# LB-word-oscillator.net
KiCad netlist of a schematic drawn in Altium Designer
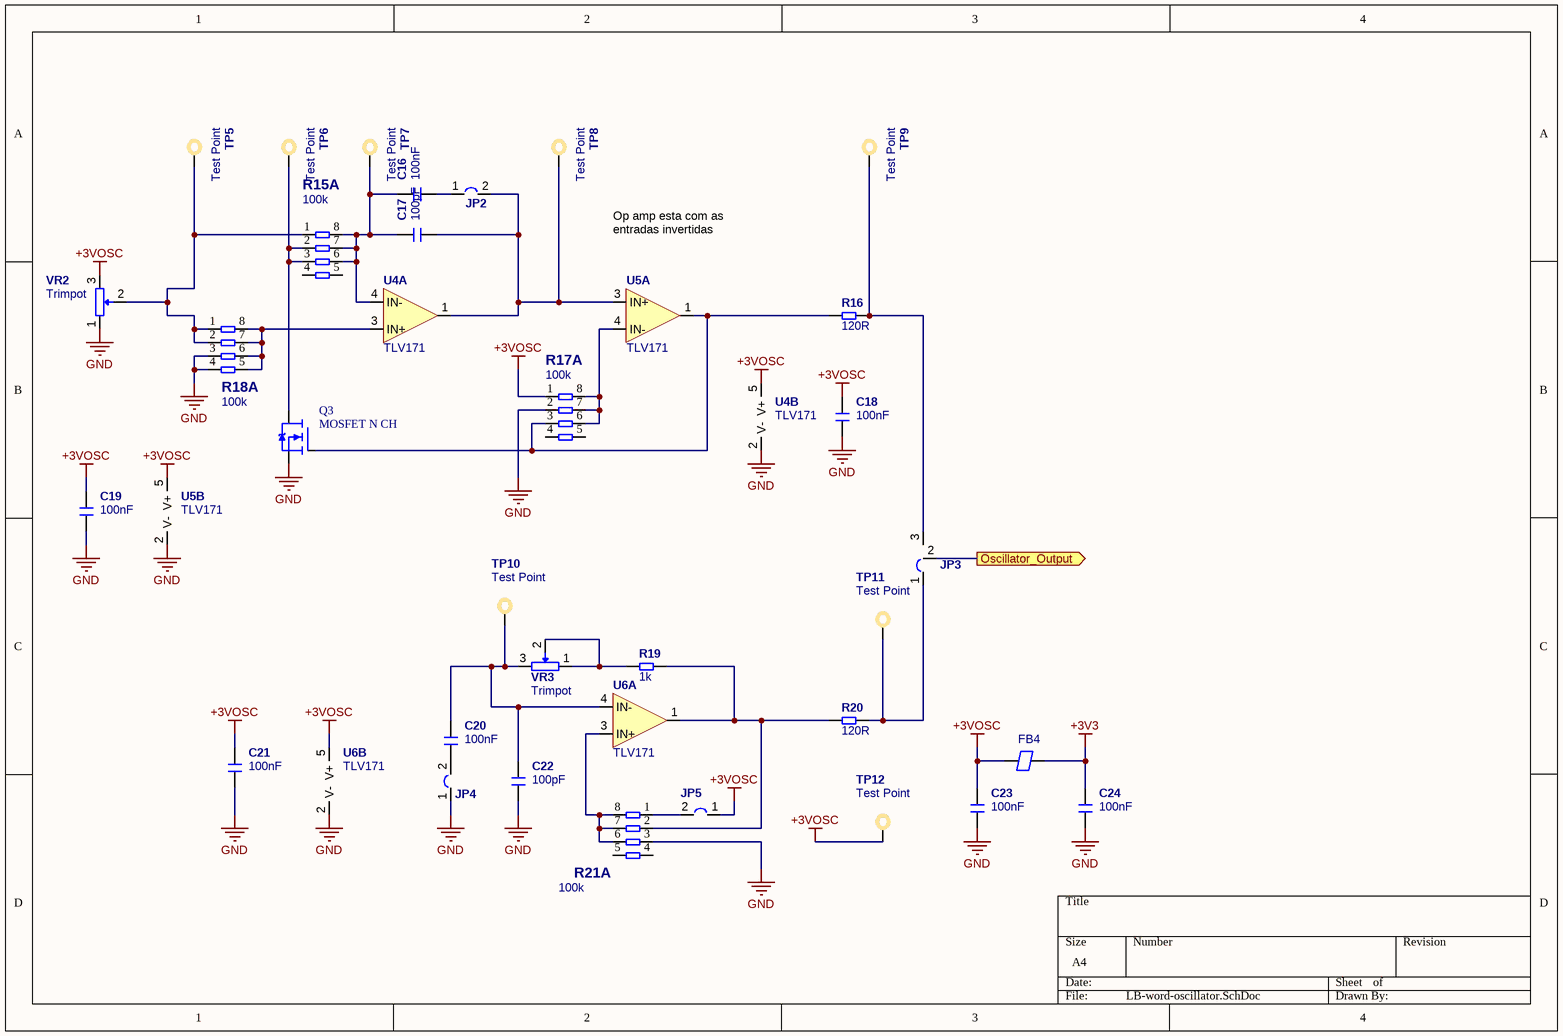
[diagram p0: LB-word-oscillator.SchDoc]

(export (version "E")
  (design (tool "Eeschema 10.0.6"))
  (components
    (comp (ref "C16")
      (value "100nF")
      (footprint "C0603_N")
      (description "Capacitor MLCC")
      (fields
        (field (name "MANUFACTURER") "Yageo")
        (field (name "MANUFACTURER PART NUMBER") "CC0603KRX7R9BB104")
      )
      (libsource (lib "wes") (part "Capacitor"))
    )
    (comp (ref "C17")
      (value "100pF")
      (footprint "C0603_N")
      (description "Capacitor MLCC")
      (fields
        (field (name "MANUFACTURER") "Yageo")
        (field (name "MANUFACTURER PART NUMBER") "CC0603KRX7R9BB104")
      )
      (libsource (lib "wes") (part "Capacitor"))
    )
    (comp (ref "C18")
      (value "100nF")
      (footprint "C0603_N")
      (description "Capacitor MLCC")
      (fields
        (field (name "MANUFACTURER") "Yageo")
        (field (name "MANUFACTURER PART NUMBER") "CC0603KRX7R9BB104")
      )
      (libsource (lib "wes") (part "Capacitor"))
    )
    (comp (ref "C19")
      (value "100nF")
      (footprint "C0603_N")
      (description "Capacitor MLCC")
      (fields
        (field (name "MANUFACTURER") "Yageo")
        (field (name "MANUFACTURER PART NUMBER") "CC0603KRX7R9BB104")
      )
      (libsource (lib "wes") (part "Capacitor"))
    )
    (comp (ref "C20")
      (value "100nF")
      (footprint "C0603_N")
      (description "Capacitor MLCC")
      (fields
        (field (name "MANUFACTURER") "Yageo")
        (field (name "MANUFACTURER PART NUMBER") "CC0603KRX7R9BB104")
      )
      (libsource (lib "wes") (part "Capacitor"))
    )
    (comp (ref "C21")
      (value "100nF")
      (footprint "C0603_N")
      (description "Capacitor MLCC")
      (fields
        (field (name "MANUFACTURER") "Yageo")
        (field (name "MANUFACTURER PART NUMBER") "CC0603KRX7R9BB104")
      )
      (libsource (lib "wes") (part "Capacitor"))
    )
    (comp (ref "C22")
      (value "100pF")
      (footprint "C0603_N")
      (description "Capacitor MLCC")
      (fields
        (field (name "MANUFACTURER") "Yageo")
        (field (name "MANUFACTURER PART NUMBER") "CC0603KRX7R9BB104")
      )
      (libsource (lib "wes") (part "Capacitor"))
    )
    (comp (ref "C23")
      (value "100nF")
      (footprint "C0603_N")
      (description "Capacitor MLCC")
      (fields
        (field (name "MANUFACTURER") "Yageo")
        (field (name "MANUFACTURER PART NUMBER") "CC0603KRX7R9BB104")
      )
      (libsource (lib "wes") (part "Capacitor"))
    )
    (comp (ref "C24")
      (value "100nF")
      (footprint "C0603_N")
      (description "Capacitor MLCC")
      (fields
        (field (name "MANUFACTURER") "Yageo")
        (field (name "MANUFACTURER PART NUMBER") "CC0603KRX7R9BB104")
      )
      (libsource (lib "wes") (part "Capacitor"))
    )
    (comp (ref "FB4")
      (value "Ferrite Bead")
      (footprint "F0603_N")
      (libsource (lib "wes") (part "Ferrite Bead"))
    )
    (comp (ref "JP2")
      (value "Jumper 2W")
      (footprint "Jumper SMD 2W NO")
      (libsource (lib "") (part "Jumper 2W_1"))
    )
    (comp (ref "JP3")
      (value "Jumper 3W")
      (footprint "Jumper SMD 3W NO")
      (libsource (lib "wes") (part "Jumper 3W"))
    )
    (comp (ref "JP4")
      (value "Jumper 2W")
      (footprint "Jumper SMD 2W NO")
      (libsource (lib "") (part "Jumper 2W_1"))
    )
    (comp (ref "JP5")
      (value "Jumper 2W")
      (footprint "Jumper SMD 2W NO")
      (libsource (lib "wes") (part "Jumper 2W"))
    )
    (comp (ref "Q3") (value "MOSFET N CH") (footprint "SOT23_N") (libsource (lib "wes") (part "MOSFET N CH")))
    (comp (ref "R15")
      (value "100k")
      (footprint "YC164")
      (fields (field (name "Comment") "; 100k"))
      (libsource (lib "wes") (part "Resistor Array - 4P"))
    )
    (comp (ref "R16")
      (value "120R")
      (footprint "R0603")
      (fields (field (name "PUBLISHER") "Altium Limited"))
      (libsource (lib "wes") (part "Resistor"))
    )
    (comp (ref "R17")
      (value "100k")
      (footprint "YC164")
      (fields (field (name "Comment") "; 100k"))
      (libsource (lib "wes") (part "Resistor Array - 4P"))
    )
    (comp (ref "R18")
      (value "100k")
      (footprint "YC164")
      (fields (field (name "Comment") "; 100k"))
      (libsource (lib "wes") (part "Resistor Array - 4P"))
    )
    (comp (ref "R19")
      (value "1k")
      (footprint "R0603")
      (fields (field (name "PUBLISHER") "Altium Limited"))
      (libsource (lib "wes") (part "Resistor"))
    )
    (comp (ref "R20")
      (value "120R")
      (footprint "R0603")
      (fields (field (name "PUBLISHER") "Altium Limited"))
      (libsource (lib "wes") (part "Resistor"))
    )
    (comp (ref "R21")
      (value "100k")
      (footprint "YC164")
      (fields (field (name "Comment") "; 100k"))
      (libsource (lib "wes") (part "Resistor Array - 4P"))
    )
    (comp (ref "TP5")
      (value "Test Point")
      (footprint "TestPoint-1.2mm")
      (libsource (lib "wes") (part "Test Point"))
    )
    (comp (ref "TP6")
      (value "Test Point")
      (footprint "TestPoint-1.2mm")
      (libsource (lib "wes") (part "Test Point"))
    )
    (comp (ref "TP7")
      (value "Test Point")
      (footprint "TestPoint-1.2mm")
      (libsource (lib "wes") (part "Test Point"))
    )
    (comp (ref "TP8")
      (value "Test Point")
      (footprint "TestPoint-1.2mm")
      (libsource (lib "wes") (part "Test Point"))
    )
    (comp (ref "TP9")
      (value "Test Point")
      (footprint "TestPoint-1.2mm")
      (libsource (lib "wes") (part "Test Point"))
    )
    (comp (ref "TP10")
      (value "Test Point")
      (footprint "TestPoint-1.2mm")
      (libsource (lib "wes") (part "Test Point"))
    )
    (comp (ref "TP11")
      (value "Test Point")
      (footprint "TestPoint-1.2mm")
      (libsource (lib "wes") (part "Test Point"))
    )
    (comp (ref "TP12")
      (value "Test Point")
      (footprint "TestPoint-1.2mm")
      (libsource (lib "wes") (part "Test Point"))
    )
    (comp (ref "U4")
      (value "TLV171")
      (footprint "SOT23-5_N")
      (description "Single RRO Opamp")
      (libsource (lib "wes") (part "TLV171"))
    )
    (comp (ref "U5")
      (value "TLV171")
      (footprint "SOT23-5_N")
      (description "Single RRO Opamp")
      (libsource (lib "wes") (part "TLV171"))
    )
    (comp (ref "U6")
      (value "TLV171")
      (footprint "SOT23-5_N")
      (description "Single RRO Opamp")
      (libsource (lib "wes") (part "TLV171"))
    )
    (comp (ref "VR2") (value "Trimpot") (footprint "Trimpot 3314") (libsource (lib "wes") (part "Trimpot")))
    (comp (ref "VR3") (value "Trimpot") (footprint "Trimpot 3314") (libsource (lib "wes") (part "Trimpot")))
  )
  (nets
    (net (code "1") (name "+3V3") (class "Default")
      (node (ref "C24") (pin "1") (pintype "passive"))
      (node (ref "FB4") (pin "2") (pinfunction "2_2") (pintype "passive"))
    )
    (net (code "2") (name "+3VOSC") (class "Default")
      (node (ref "C18") (pin "1") (pintype "passive"))
      (node (ref "C19") (pin "1") (pintype "passive"))
      (node (ref "C21") (pin "1") (pintype "passive"))
      (node (ref "C23") (pin "1") (pintype "passive"))
      (node (ref "FB4") (pin "1") (pinfunction "1_1") (pintype "passive"))
      (node (ref "JP5") (pin "1") (pinfunction "1_1") (pintype "passive"))
      (node (ref "R17") (pin "1") (pinfunction "1_1") (pintype "passive"))
      (node (ref "TP12") (pin "1") (pinfunction "1_1") (pintype "passive"))
      (node (ref "U4") (pin "5") (pinfunction "V+_5") (pintype "passive"))
      (node (ref "U5") (pin "5") (pinfunction "V+_5") (pintype "passive"))
      (node (ref "U6") (pin "5") (pinfunction "V+_5") (pintype "passive"))
      (node (ref "VR2") (pin "3") (pinfunction "3_3") (pintype "passive"))
    )
    (net (code "3") (name "/Oscillator_Output") (class "Default")
      (node (ref "JP3") (pin "2") (pinfunction "2_2") (pintype "passive"))
    )
    (net (code "4") (name "GND") (class "Default")
      (node (ref "C18") (pin "2") (pintype "passive"))
      (node (ref "C19") (pin "2") (pintype "passive"))
      (node (ref "C21") (pin "2") (pintype "passive"))
      (node (ref "C22") (pin "2") (pintype "passive"))
      (node (ref "C23") (pin "2") (pintype "passive"))
      (node (ref "C24") (pin "2") (pintype "passive"))
      (node (ref "JP4") (pin "1") (pinfunction "1_1") (pintype "passive"))
      (node (ref "Q3") (pin "3") (pinfunction "S_3") (pintype "passive"))
      (node (ref "R17") (pin "3") (pinfunction "3_3") (pintype "passive"))
      (node (ref "R17") (pin "4") (pinfunction "4_4") (pintype "passive"))
      (node (ref "R18") (pin "2") (pinfunction "2_2") (pintype "passive"))
      (node (ref "R21") (pin "3") (pinfunction "3_3") (pintype "passive"))
      (node (ref "U4") (pin "2") (pinfunction "V-_2") (pintype "passive"))
      (node (ref "U5") (pin "2") (pinfunction "V-_2") (pintype "passive"))
      (node (ref "U6") (pin "2") (pinfunction "V-_2") (pintype "passive"))
      (node (ref "VR2") (pin "1") (pinfunction "1_1") (pintype "passive"))
    )
    (net (code "5") (name "Net-(C16-Pad2)") (class "Default")
      (node (ref "C16") (pin "2") (pintype "passive"))
      (node (ref "JP2") (pin "1") (pinfunction "1_1") (pintype "passive"))
    )
    (net (code "6") (name "Net-(C20-Pad2)") (class "Default")
      (node (ref "C20") (pin "2") (pintype "passive"))
      (node (ref "JP4") (pin "2") (pinfunction "2_2") (pintype "passive"))
    )
    (net (code "7") (name "Net-(JP3-Pad1)") (class "Default")
      (node (ref "JP3") (pin "1") (pinfunction "1_1") (pintype "passive"))
      (node (ref "R20") (pin "2") (pinfunction "2_2") (pintype "passive"))
      (node (ref "TP11") (pin "1") (pinfunction "1_1") (pintype "passive"))
    )
    (net (code "8") (name "Net-(JP3-Pad3)") (class "Default")
      (node (ref "JP3") (pin "3") (pinfunction "3_3") (pintype "passive"))
      (node (ref "R16") (pin "2") (pinfunction "2_2") (pintype "passive"))
      (node (ref "TP9") (pin "1") (pinfunction "1_1") (pintype "passive"))
    )
    (net (code "9") (name "Net-(JP5-Pad2)") (class "Default")
      (node (ref "JP5") (pin "2") (pinfunction "2_2") (pintype "passive"))
      (node (ref "R21") (pin "1") (pinfunction "1_1") (pintype "passive"))
    )
    (net (code "10") (name "Net-(Q3-D)") (class "Default")
      (node (ref "Q3") (pin "2") (pinfunction "D_2") (pintype "passive"))
      (node (ref "R15") (pin "2") (pinfunction "2_2") (pintype "passive"))
      (node (ref "R15") (pin "3") (pinfunction "3_3") (pintype "passive"))
      (node (ref "TP6") (pin "1") (pinfunction "1_1") (pintype "passive"))
    )
    (net (code "11") (name "Net-(Q3-G)") (class "Default")
      (node (ref "Q3") (pin "1") (pinfunction "G_1") (pintype "passive"))
      (node (ref "R16") (pin "1") (pinfunction "1_1") (pintype "passive"))
      (node (ref "R18") (pin "3") (pinfunction "3_3") (pintype "passive"))
      (node (ref "U5") (pin "1") (pinfunction "OUT_1") (pintype "passive"))
    )
    (net (code "12") (name "Net-(R15-Pad1)") (class "Default")
      (node (ref "R15") (pin "1") (pinfunction "1_1") (pintype "passive"))
      (node (ref "R17") (pin "2") (pinfunction "2_2") (pintype "passive"))
      (node (ref "R18") (pin "1") (pinfunction "1_1") (pintype "passive"))
      (node (ref "TP5") (pin "1") (pinfunction "1_1") (pintype "passive"))
      (node (ref "VR2") (pin "2") (pinfunction "2_2") (pintype "passive"))
    )
    (net (code "13") (name "Net-(R19-Pad1)") (class "Default")
      (node (ref "R19") (pin "1") (pinfunction "1_1") (pintype "passive"))
      (node (ref "VR3") (pin "1") (pinfunction "1_1") (pintype "passive"))
      (node (ref "VR3") (pin "2") (pinfunction "2_2") (pintype "passive"))
    )
    (net (code "14") (name "Net-(U4A-IN+)") (class "Default")
      (node (ref "R17") (pin "5") (pinfunction "5_5") (pintype "passive"))
      (node (ref "R17") (pin "6") (pinfunction "6_6") (pintype "passive"))
      (node (ref "R17") (pin "7") (pinfunction "7_7") (pintype "passive"))
      (node (ref "R18") (pin "8") (pinfunction "8_8") (pintype "passive"))
      (node (ref "U4") (pin "3") (pinfunction "IN+_3") (pintype "passive"))
    )
    (net (code "15") (name "Net-(U4A-IN-)") (class "Default")
      (node (ref "C16") (pin "1") (pintype "passive"))
      (node (ref "C17") (pin "1") (pintype "passive"))
      (node (ref "R15") (pin "6") (pinfunction "6_6") (pintype "passive"))
      (node (ref "R15") (pin "7") (pinfunction "7_7") (pintype "passive"))
      (node (ref "R15") (pin "8") (pinfunction "8_8") (pintype "passive"))
      (node (ref "TP7") (pin "1") (pinfunction "1_1") (pintype "passive"))
      (node (ref "U4") (pin "4") (pinfunction "IN-_4") (pintype "passive"))
    )
    (net (code "16") (name "Net-(U4A-OUT)") (class "Default")
      (node (ref "C17") (pin "2") (pintype "passive"))
      (node (ref "JP2") (pin "2") (pinfunction "2_2") (pintype "passive"))
      (node (ref "TP8") (pin "1") (pinfunction "1_1") (pintype "passive"))
      (node (ref "U4") (pin "1") (pinfunction "OUT_1") (pintype "passive"))
      (node (ref "U5") (pin "3") (pinfunction "IN+_3") (pintype "passive"))
    )
    (net (code "17") (name "Net-(U5A-IN-)") (class "Default")
      (node (ref "R17") (pin "8") (pinfunction "8_8") (pintype "passive"))
      (node (ref "R18") (pin "6") (pinfunction "6_6") (pintype "passive"))
      (node (ref "R18") (pin "7") (pinfunction "7_7") (pintype "passive"))
      (node (ref "U5") (pin "4") (pinfunction "IN-_4") (pintype "passive"))
    )
    (net (code "18") (name "Net-(U6A-IN+)") (class "Default")
      (node (ref "R21") (pin "6") (pinfunction "6_6") (pintype "passive"))
      (node (ref "R21") (pin "7") (pinfunction "7_7") (pintype "passive"))
      (node (ref "R21") (pin "8") (pinfunction "8_8") (pintype "passive"))
      (node (ref "U6") (pin "3") (pinfunction "IN+_3") (pintype "passive"))
    )
    (net (code "19") (name "Net-(U6A-IN-)") (class "Default")
      (node (ref "C20") (pin "1") (pintype "passive"))
      (node (ref "C22") (pin "1") (pintype "passive"))
      (node (ref "TP10") (pin "1") (pinfunction "1_1") (pintype "passive"))
      (node (ref "U6") (pin "4") (pinfunction "IN-_4") (pintype "passive"))
      (node (ref "VR3") (pin "3") (pinfunction "3_3") (pintype "passive"))
    )
    (net (code "20") (name "Net-(U6A-OUT)") (class "Default")
      (node (ref "R19") (pin "2") (pinfunction "2_2") (pintype "passive"))
      (node (ref "R20") (pin "1") (pinfunction "1_1") (pintype "passive"))
      (node (ref "R21") (pin "2") (pinfunction "2_2") (pintype "passive"))
      (node (ref "U6") (pin "1") (pinfunction "OUT_1") (pintype "passive"))
    )
    (net (code "21") (name "unconnected-(R15-Pad4)") (class "Default")
      (node (ref "R15") (pin "4") (pinfunction "4_4") (pintype "passive"))
    )
    (net (code "22") (name "unconnected-(R15-Pad5)") (class "Default")
      (node (ref "R15") (pin "5") (pinfunction "5_5") (pintype "passive"))
    )
    (net (code "23") (name "unconnected-(R18-Pad4)") (class "Default")
      (node (ref "R18") (pin "4") (pinfunction "4_4") (pintype "passive"))
    )
    (net (code "24") (name "unconnected-(R18-Pad5)") (class "Default")
      (node (ref "R18") (pin "5") (pinfunction "5_5") (pintype "passive"))
    )
    (net (code "25") (name "unconnected-(R21-Pad4)") (class "Default")
      (node (ref "R21") (pin "4") (pinfunction "4_4") (pintype "passive"))
    )
    (net (code "26") (name "unconnected-(R21-Pad5)") (class "Default")
      (node (ref "R21") (pin "5") (pinfunction "5_5") (pintype "passive"))
    )
  )
)
